# CamBienSieuAm_SRF05.net
KiCad netlist of a schematic drawn in Altium Designer
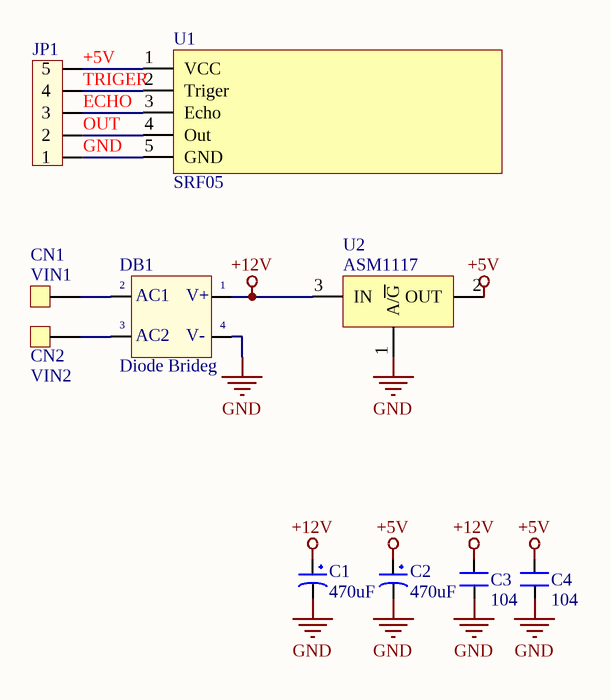
[diagram p0: CamBienSieuAm SRF05.SchDoc]

(export (version "E")
  (design (tool "Eeschema 10.0.6"))
  (components
    (comp (ref "C1")
      (value "470uF")
      (footprint "C-ALU-D6.5")
      (description "Cap P  0,1uF < 22uF , 16 - 50V")
      (libsource (lib "PART") (part "CP1"))
    )
    (comp (ref "C2")
      (value "470uF")
      (footprint "C-ALU-D6.5")
      (description "Cap P  0,1uF < 22uF , 16 - 50V")
      (libsource (lib "PART") (part "CP1"))
    )
    (comp (ref "C3")
      (value "104")
      (footprint "C-0805")
      (fields (field (name "DESIGNED BY") "VanDungEvn"))
      (libsource (lib "syhaunguyen") (part "CN"))
    )
    (comp (ref "C4")
      (value "104")
      (footprint "C-0805")
      (fields (field (name "DESIGNED BY") "VanDungEvn"))
      (libsource (lib "syhaunguyen") (part "CN"))
    )
    (comp (ref "CN1")
      (value "VIN1")
      (footprint "M3")
      (libsource (lib "doAnTotNghiep2017Lib") (part "COCDONGM3"))
    )
    (comp (ref "CN2")
      (value "VIN2")
      (footprint "M3")
      (libsource (lib "doAnTotNghiep2017Lib") (part "COCDONGM3"))
    )
    (comp (ref "DB1")
      (value "Diode Brideg")
      (footprint "D-DB-1A-SMD")
      (description "Convert AC to DC voltage, 4 pin")
      (libsource (lib "PART") (part "DB"))
    )
    (comp (ref "JP1") (value "JP5") (footprint "JP5") (libsource (lib "syhaunguyen") (part "JP5")))
    (comp (ref "U1") (value "SRF05") (libsource (lib "MrQuan") (part "SRF05")))
    (comp (ref "U2")
      (value "ASM1117")
      (footprint "TO-252")
      (libsource (lib "doAnTotNghiep2017Lib") (part "ASM1117"))
    )
  )
  (nets
    (net (code "1") (name "+5V") (class "Default")
      (node (ref "C2") (pin "1") (pinfunction "1_1") (pintype "passive"))
      (node (ref "C4") (pin "2") (pinfunction "2_2") (pintype "passive"))
      (node (ref "JP1") (pin "5") (pinfunction "5_5") (pintype "passive"))
      (node (ref "U1") (pin "1") (pinfunction "VCC_1") (pintype "passive"))
      (node (ref "U2") (pin "2") (pinfunction "OUT_2") (pintype "passive"))
    )
    (net (code "2") (name "+12V") (class "Default")
      (node (ref "C1") (pin "1") (pinfunction "1_1") (pintype "passive"))
      (node (ref "C3") (pin "2") (pinfunction "2_2") (pintype "passive"))
      (node (ref "DB1") (pin "3") (pinfunction "AC2_3") (pintype "passive"))
      (node (ref "U2") (pin "3") (pinfunction "IN_3") (pintype "passive"))
    )
    (net (code "3") (name "/ECHO") (class "Default")
      (node (ref "JP1") (pin "3") (pinfunction "3_3") (pintype "passive"))
      (node (ref "U1") (pin "3") (pinfunction "Echo_3") (pintype "passive"))
    )
    (net (code "4") (name "/OUT") (class "Default")
      (node (ref "JP1") (pin "2") (pinfunction "2_2") (pintype "passive"))
      (node (ref "U1") (pin "4") (pinfunction "Out_4") (pintype "passive"))
    )
    (net (code "5") (name "/TRIGER") (class "Default")
      (node (ref "JP1") (pin "4") (pinfunction "4_4") (pintype "passive"))
      (node (ref "U1") (pin "2") (pinfunction "Triger_2") (pintype "passive"))
    )
    (net (code "6") (name "GND") (class "Default")
      (node (ref "C1") (pin "2") (pinfunction "2_2") (pintype "passive"))
      (node (ref "C2") (pin "2") (pinfunction "2_2") (pintype "passive"))
      (node (ref "C3") (pin "1") (pinfunction "1_1") (pintype "passive"))
      (node (ref "C4") (pin "1") (pinfunction "1_1") (pintype "passive"))
      (node (ref "DB1") (pin "4") (pinfunction "-V_OUT_4") (pintype "passive"))
      (node (ref "JP1") (pin "1") (pinfunction "1_1") (pintype "passive"))
      (node (ref "U1") (pin "5") (pinfunction "GND_5") (pintype "passive"))
      (node (ref "U2") (pin "1") (pinfunction "A/~{G}_1") (pintype "passive"))
    )
    (net (code "7") (name "Net-(DB1-+V_OUT)") (class "Default")
      (node (ref "CN2") (pin "1") (pintype "passive"))
      (node (ref "DB1") (pin "1") (pinfunction "+V_OUT_1") (pintype "passive"))
    )
    (net (code "8") (name "Net-(DB1-AC1)") (class "Default")
      (node (ref "CN1") (pin "1") (pintype "passive"))
      (node (ref "DB1") (pin "2") (pinfunction "AC1_2") (pintype "passive"))
    )
  )
)
